# hud_v300_CONN.net
KiCad netlist of a schematic drawn in Altium Designer
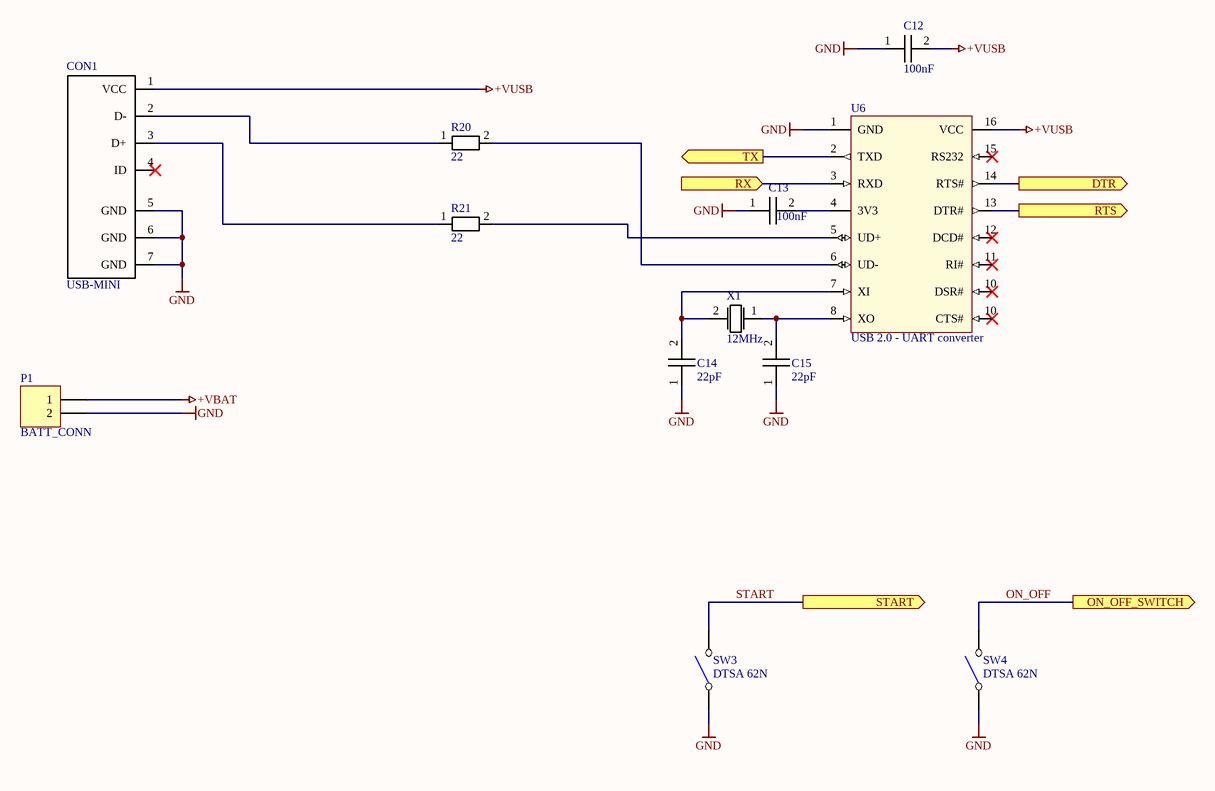
[diagram p0: hud_v300_CONN.SchDoc]

(export (version "E")
  (design (tool "Eeschema 10.0.6"))
  (components
    (comp (ref "C12") (value "100nF") (footprint "0805_C") (libsource (lib "Schlib1") (part "CAPACITOR")))
    (comp (ref "C13") (value "100nF") (footprint "0805_C") (libsource (lib "Schlib1") (part "CAPACITOR")))
    (comp (ref "C14") (value "22pF") (footprint "0805_C") (libsource (lib "Schlib1") (part "CAPACITOR")))
    (comp (ref "C15") (value "22pF") (footprint "0805_C") (libsource (lib "Schlib1") (part "CAPACITOR")))
    (comp (ref "CON1")
      (value "USB-MINI")
      (footprint "USB-MINI")
      (libsource (lib "Schlib1") (part "USB-MINI"))
    )
    (comp (ref "P1")
      (value "BATT_CONN")
      (footprint "HDR1X2")
      (description "Header, 2-Pin")
      (fields (field (name "PUBLISHER") "Altium Limited"))
      (libsource (lib "Miscellaneous Connectors") (part "Header 2"))
    )
    (comp (ref "R20") (value "22") (footprint "0805") (libsource (lib "Schlib1") (part "RESISTOR")))
    (comp (ref "R21") (value "22") (footprint "0805") (libsource (lib "Schlib1") (part "RESISTOR")))
    (comp (ref "SW3")
      (value "DTSA 62N")
      (footprint "SW_DTSA-62N")
      (libsource (lib "Schlib1") (part "SW_DTSA 62N"))
    )
    (comp (ref "SW4")
      (value "DTSA 62N")
      (footprint "SW_DTSA-62N")
      (libsource (lib "Schlib1") (part "SW_DTSA 62N"))
    )
    (comp (ref "U6")
      (value "USB 2.0 - UART converter")
      (footprint "SOP127P660X265-16N")
      (libsource (lib "ic_modules") (part "CH340G"))
    )
    (comp (ref "X1") (value "12MHz") (footprint "XTAL_SMALL") (libsource (lib "Schlib1") (part "XTAL")))
  )
  (nets
    (net (code "1") (name "+VBAT") (class "Default")
      (node (ref "P1") (pin "1") (pinfunction "1_1") (pintype "passive"))
    )
    (net (code "2") (name "+VUSB") (class "Default")
      (node (ref "C12") (pin "2") (pinfunction "2_2") (pintype "passive"))
      (node (ref "CON1") (pin "1") (pinfunction "VCC_1") (pintype "power_in"))
      (node (ref "U6") (pin "16") (pinfunction "VCC_16") (pintype "power_in"))
    )
    (net (code "3") (name "/DTR") (class "Default")
      (node (ref "U6") (pin "14") (pinfunction "RTS#_14") (pintype "output"))
    )
    (net (code "4") (name "/ON_OFF") (class "Default")
      (node (ref "SW4") (pin "2") (pinfunction "2_2") (pintype "passive"))
    )
    (net (code "5") (name "/RTS") (class "Default")
      (node (ref "U6") (pin "13") (pinfunction "DTR#_13") (pintype "output"))
    )
    (net (code "6") (name "/RX") (class "Default")
      (node (ref "U6") (pin "3") (pinfunction "RXD_3") (pintype "input"))
    )
    (net (code "7") (name "/START") (class "Default")
      (node (ref "SW3") (pin "2") (pinfunction "2_2") (pintype "passive"))
    )
    (net (code "8") (name "/TX") (class "Default")
      (node (ref "U6") (pin "2") (pinfunction "TXD_2") (pintype "output"))
    )
    (net (code "9") (name "GND") (class "Default")
      (node (ref "C12") (pin "1") (pinfunction "1_1") (pintype "passive"))
      (node (ref "C13") (pin "1") (pinfunction "1_1") (pintype "passive"))
      (node (ref "C14") (pin "1") (pinfunction "1_1") (pintype "passive"))
      (node (ref "C15") (pin "1") (pinfunction "1_1") (pintype "passive"))
      (node (ref "CON1") (pin "5") (pinfunction "GND_5") (pintype "passive"))
      (node (ref "CON1") (pin "6") (pinfunction "GND_6") (pintype "passive"))
      (node (ref "CON1") (pin "7") (pinfunction "GND_7") (pintype "passive"))
      (node (ref "P1") (pin "2") (pinfunction "2_2") (pintype "passive"))
      (node (ref "SW3") (pin "1") (pinfunction "1_1") (pintype "passive"))
      (node (ref "SW4") (pin "1") (pinfunction "1_1") (pintype "passive"))
      (node (ref "U6") (pin "1") (pinfunction "GND_1") (pintype "power_in"))
    )
    (net (code "10") (name "Net-(CON1-D+)") (class "Default")
      (node (ref "CON1") (pin "3") (pinfunction "D+_3") (pintype "passive"))
      (node (ref "R21") (pin "1") (pinfunction "0_1") (pintype "passive"))
    )
    (net (code "11") (name "Net-(CON1-D-)") (class "Default")
      (node (ref "CON1") (pin "2") (pinfunction "D-_2") (pintype "passive"))
      (node (ref "R20") (pin "1") (pinfunction "0_1") (pintype "passive"))
    )
    (net (code "12") (name "Net-(R20-1)") (class "Default")
      (node (ref "R20") (pin "2") (pinfunction "1_2") (pintype "passive"))
      (node (ref "U6") (pin "6") (pinfunction "UD-_6") (pintype "bidirectional"))
    )
    (net (code "13") (name "Net-(R21-1)") (class "Default")
      (node (ref "R21") (pin "2") (pinfunction "1_2") (pintype "passive"))
      (node (ref "U6") (pin "5") (pinfunction "UD+_5") (pintype "bidirectional"))
    )
    (net (code "14") (name "Net-(U6-3V3)") (class "Default")
      (node (ref "C13") (pin "2") (pinfunction "2_2") (pintype "passive"))
      (node (ref "U6") (pin "4") (pinfunction "3V3_4") (pintype "power_in"))
    )
    (net (code "15") (name "Net-(U6-XI)") (class "Default")
      (node (ref "C14") (pin "2") (pinfunction "2_2") (pintype "passive"))
      (node (ref "U6") (pin "7") (pinfunction "XI_7") (pintype "input"))
      (node (ref "X1") (pin "2") (pinfunction "2_2") (pintype "passive"))
    )
    (net (code "16") (name "Net-(U6-XO)") (class "Default")
      (node (ref "C15") (pin "2") (pinfunction "2_2") (pintype "passive"))
      (node (ref "U6") (pin "8") (pinfunction "XO_8") (pintype "input"))
      (node (ref "X1") (pin "1") (pinfunction "1_1") (pintype "passive"))
    )
    (net (code "17") (name "unconnected-(CON1-ID-Pad4)") (class "Default")
      (node (ref "CON1") (pin "4") (pinfunction "ID_4") (pintype "passive+no_connect"))
    )
    (net (code "18") (name "unconnected-(U6-CTS#-Pad10)") (class "Default")
      (node (ref "U6") (pin "10") (pinfunction "CTS#_10") (pintype "input+no_connect"))
    )
    (net (code "19") (name "unconnected-(U6-DCD#-Pad12)") (class "Default")
      (node (ref "U6") (pin "12") (pinfunction "DCD#_12") (pintype "input+no_connect"))
    )
    (net (code "20") (name "unconnected-(U6-DSR#-Pad10)") (class "Default")
      (node (ref "U6") (pin "10") (pinfunction "DSR#_10") (pintype "input+no_connect"))
    )
    (net (code "21") (name "unconnected-(U6-RI#-Pad11)") (class "Default")
      (node (ref "U6") (pin "11") (pinfunction "RI#_11") (pintype "input+no_connect"))
    )
    (net (code "22") (name "unconnected-(U6-RS232-Pad15)") (class "Default")
      (node (ref "U6") (pin "15") (pinfunction "RS232_15") (pintype "input+no_connect"))
    )
  )
)
